# SCH_LED_bar_2021-10-13.net
KiCad netlist of a schematic drawn in EasyEDA
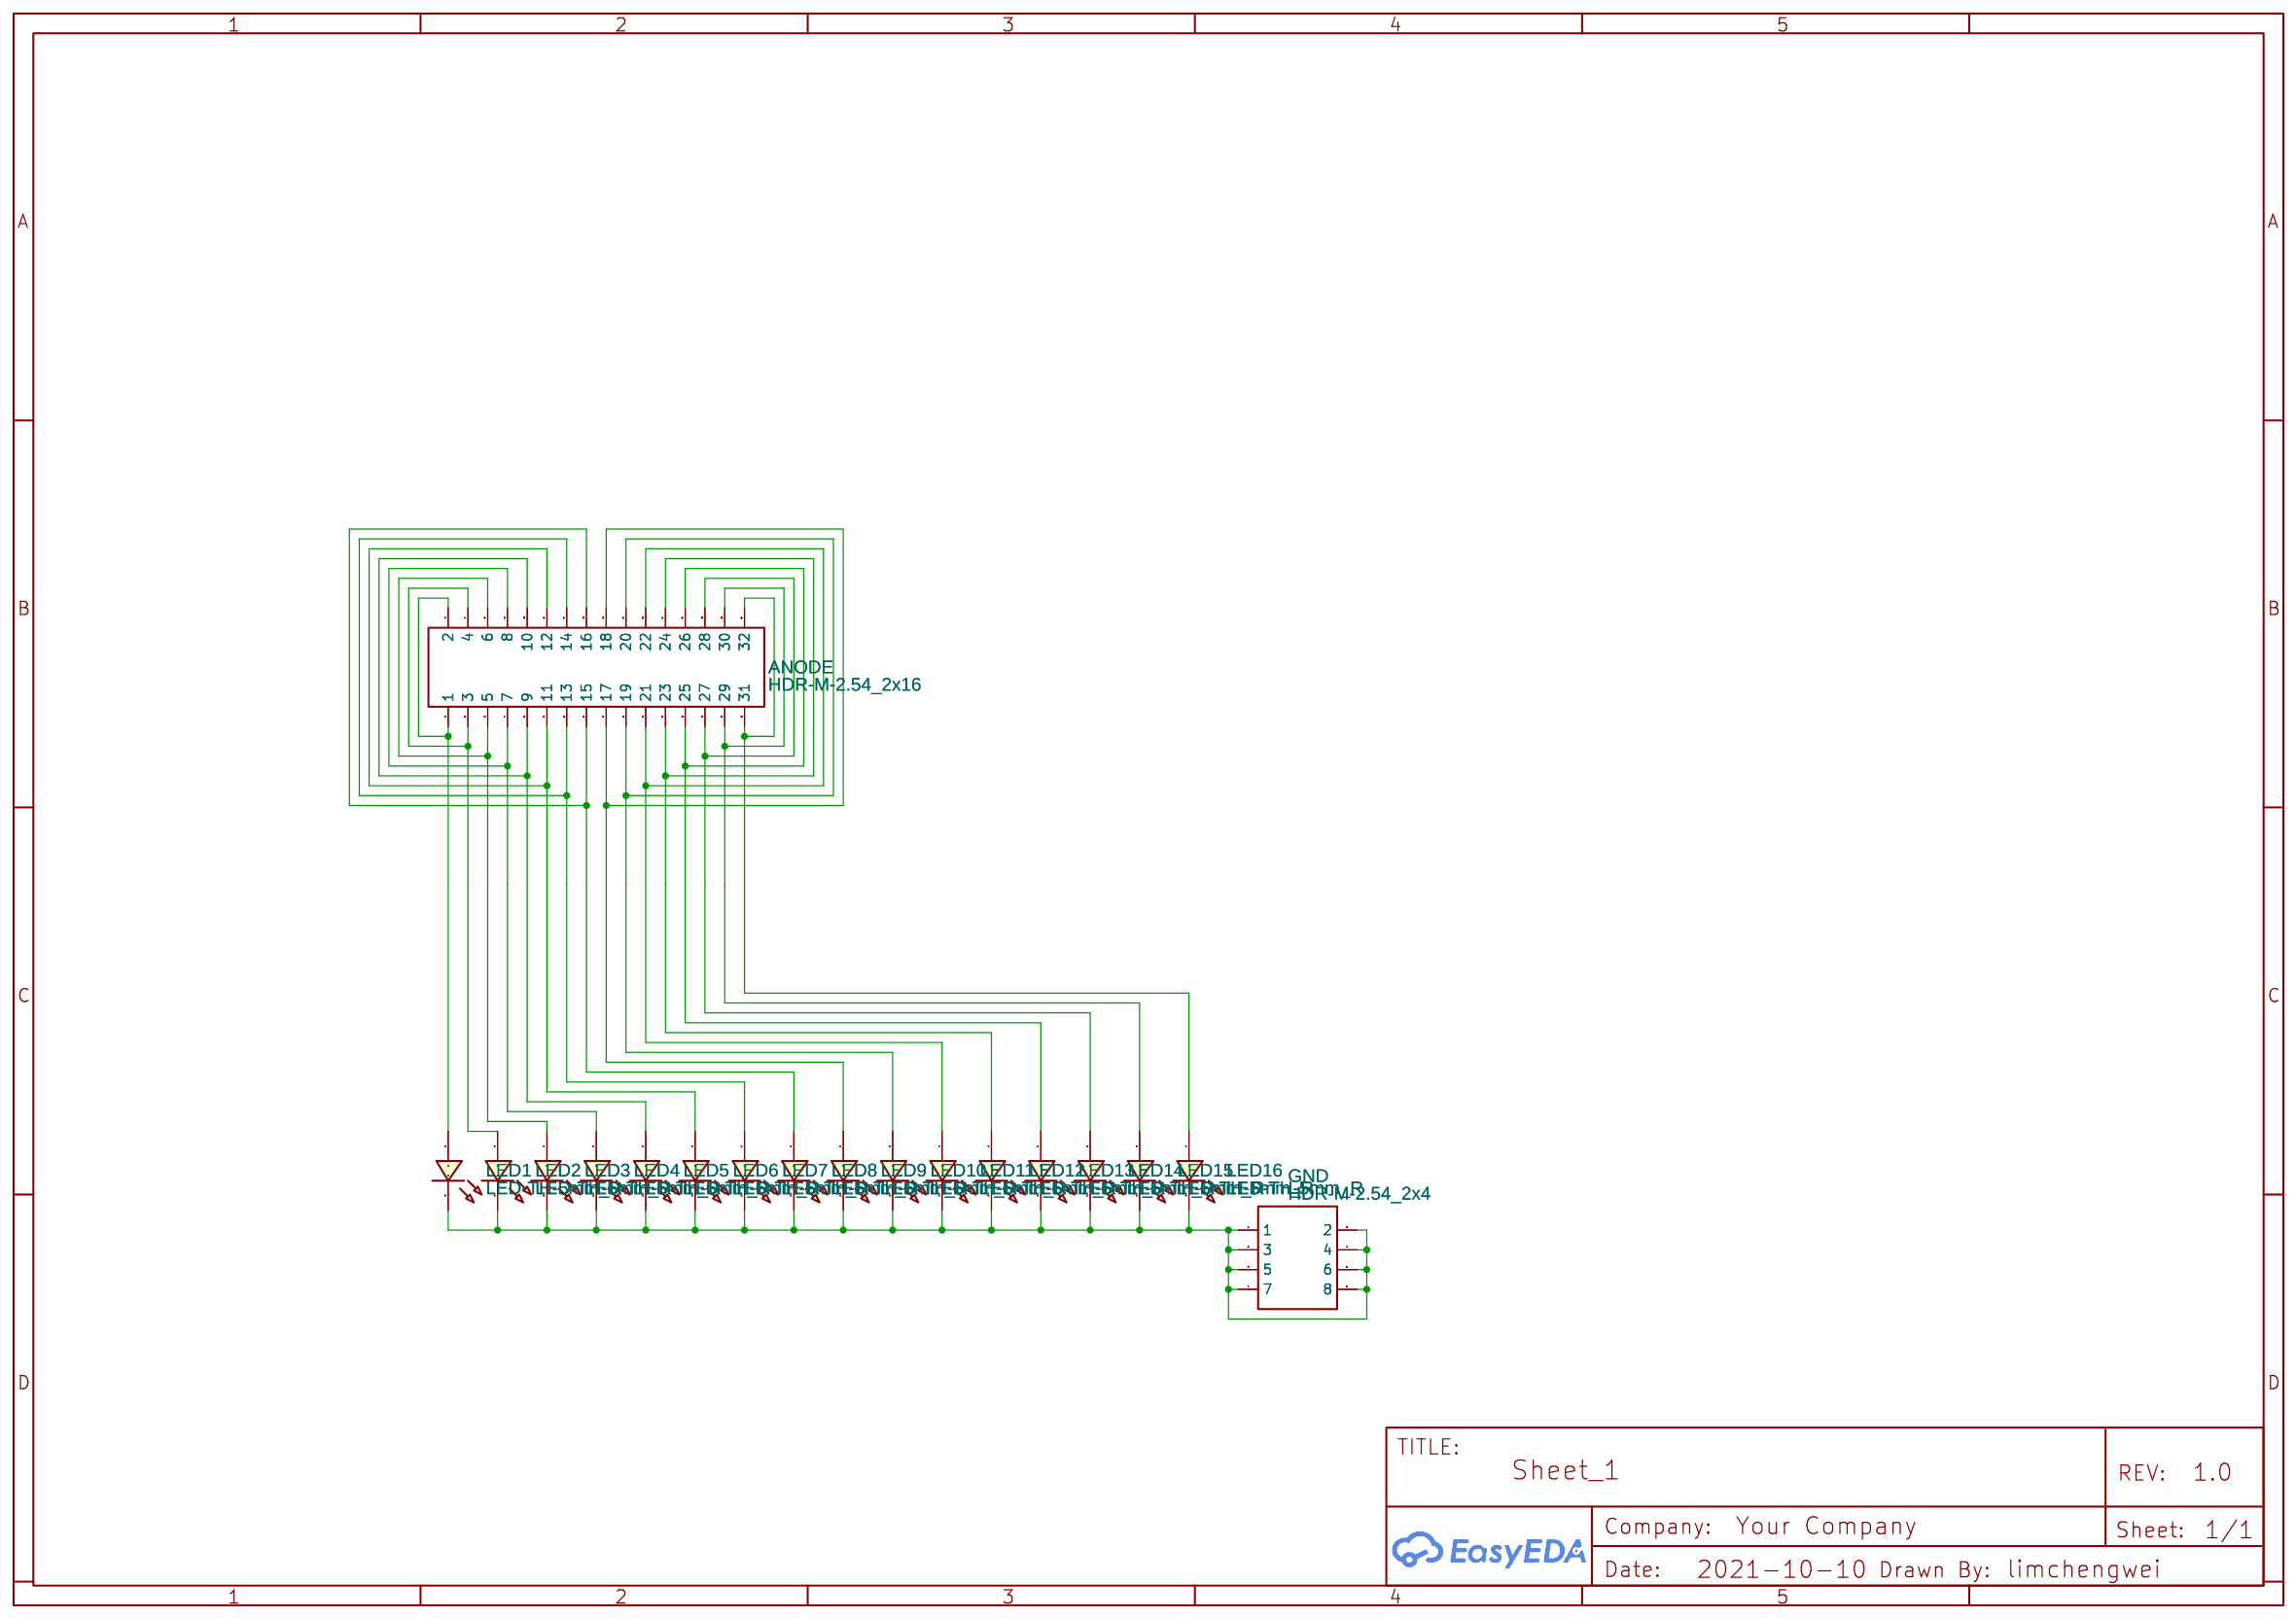
[diagram p0: schematic sheet]

(export (version "E")
  (design (tool "Eeschema 10.0.6"))
  (components
    (comp (ref "ANODE")
      (value "HDR-M-2.54_2x16")
      (fields (field (name "BOM_Supplier Part") "C124382"))
      (libsource (lib "") (part "HDR-M-2.54_2x16"))
    )
    (comp (ref "GND")
      (value "HDR-M-2.54_2x4")
      (fields (field (name "BOM_Supplier Part") "C58363"))
      (libsource (lib "") (part "HDR-M-2.54_2x4"))
    )
    (comp (ref "LED1")
      (value "LED-TH-5mm_R")
      (fields
        (field (name "BOM_Manufacturer Part") "333-2SURD/S530-A3")
        (field (name "BOM_Supplier Part") "C87271")
      )
      (libsource (lib "") (part "LED-TH-5mm_R"))
    )
    (comp (ref "LED2")
      (value "LED-TH-5mm_R")
      (fields
        (field (name "BOM_Manufacturer Part") "333-2SURD/S530-A3")
        (field (name "BOM_Supplier Part") "C87271")
      )
      (libsource (lib "") (part "LED-TH-5mm_R"))
    )
    (comp (ref "LED3")
      (value "LED-TH-5mm_R")
      (fields
        (field (name "BOM_Manufacturer Part") "333-2SURD/S530-A3")
        (field (name "BOM_Supplier Part") "C87271")
      )
      (libsource (lib "") (part "LED-TH-5mm_R"))
    )
    (comp (ref "LED4")
      (value "LED-TH-5mm_R")
      (fields
        (field (name "BOM_Manufacturer Part") "333-2SURD/S530-A3")
        (field (name "BOM_Supplier Part") "C87271")
      )
      (libsource (lib "") (part "LED-TH-5mm_R"))
    )
    (comp (ref "LED5")
      (value "LED-TH-5mm_R")
      (fields
        (field (name "BOM_Manufacturer Part") "333-2SURD/S530-A3")
        (field (name "BOM_Supplier Part") "C87271")
      )
      (libsource (lib "") (part "LED-TH-5mm_R"))
    )
    (comp (ref "LED6")
      (value "LED-TH-5mm_R")
      (fields
        (field (name "BOM_Manufacturer Part") "333-2SURD/S530-A3")
        (field (name "BOM_Supplier Part") "C87271")
      )
      (libsource (lib "") (part "LED-TH-5mm_R"))
    )
    (comp (ref "LED7")
      (value "LED-TH-5mm_R")
      (fields
        (field (name "BOM_Manufacturer Part") "333-2SURD/S530-A3")
        (field (name "BOM_Supplier Part") "C87271")
      )
      (libsource (lib "") (part "LED-TH-5mm_R"))
    )
    (comp (ref "LED8")
      (value "LED-TH-5mm_R")
      (fields
        (field (name "BOM_Manufacturer Part") "333-2SURD/S530-A3")
        (field (name "BOM_Supplier Part") "C87271")
      )
      (libsource (lib "") (part "LED-TH-5mm_R"))
    )
    (comp (ref "LED9")
      (value "LED-TH-5mm_R")
      (fields
        (field (name "BOM_Manufacturer Part") "333-2SURD/S530-A3")
        (field (name "BOM_Supplier Part") "C87271")
      )
      (libsource (lib "") (part "LED-TH-5mm_R"))
    )
    (comp (ref "LED10")
      (value "LED-TH-5mm_R")
      (fields
        (field (name "BOM_Manufacturer Part") "333-2SURD/S530-A3")
        (field (name "BOM_Supplier Part") "C87271")
      )
      (libsource (lib "") (part "LED-TH-5mm_R"))
    )
    (comp (ref "LED11")
      (value "LED-TH-5mm_R")
      (fields
        (field (name "BOM_Manufacturer Part") "333-2SURD/S530-A3")
        (field (name "BOM_Supplier Part") "C87271")
      )
      (libsource (lib "") (part "LED-TH-5mm_R"))
    )
    (comp (ref "LED12")
      (value "LED-TH-5mm_R")
      (fields
        (field (name "BOM_Manufacturer Part") "333-2SURD/S530-A3")
        (field (name "BOM_Supplier Part") "C87271")
      )
      (libsource (lib "") (part "LED-TH-5mm_R"))
    )
    (comp (ref "LED13")
      (value "LED-TH-5mm_R")
      (fields
        (field (name "BOM_Manufacturer Part") "333-2SURD/S530-A3")
        (field (name "BOM_Supplier Part") "C87271")
      )
      (libsource (lib "") (part "LED-TH-5mm_R"))
    )
    (comp (ref "LED14")
      (value "LED-TH-5mm_R")
      (fields
        (field (name "BOM_Manufacturer Part") "333-2SURD/S530-A3")
        (field (name "BOM_Supplier Part") "C87271")
      )
      (libsource (lib "") (part "LED-TH-5mm_R"))
    )
    (comp (ref "LED15")
      (value "LED-TH-5mm_R")
      (fields
        (field (name "BOM_Manufacturer Part") "333-2SURD/S530-A3")
        (field (name "BOM_Supplier Part") "C87271")
      )
      (libsource (lib "") (part "LED-TH-5mm_R"))
    )
    (comp (ref "LED16")
      (value "LED-TH-5mm_R")
      (fields
        (field (name "BOM_Manufacturer Part") "333-2SURD/S530-A3")
        (field (name "BOM_Supplier Part") "C87271")
      )
      (libsource (lib "") (part "LED-TH-5mm_R"))
    )
  )
  (nets
    (net (code "1") (name "Net-(ANODE-Pad1)") (class "Default")
      (node (ref "ANODE") (pin "1") (pinfunction "1_1") (pintype "input"))
      (node (ref "ANODE") (pin "2") (pinfunction "2_2") (pintype "input"))
      (node (ref "LED1") (pin "1") (pinfunction "1_1") (pintype "unspecified"))
    )
    (net (code "2") (name "Net-(ANODE-Pad3)") (class "Default")
      (node (ref "ANODE") (pin "3") (pinfunction "3_3") (pintype "input"))
      (node (ref "ANODE") (pin "4") (pinfunction "4_4") (pintype "input"))
      (node (ref "LED2") (pin "1") (pinfunction "1_1") (pintype "unspecified"))
    )
    (net (code "3") (name "Net-(ANODE-Pad5)") (class "Default")
      (node (ref "ANODE") (pin "5") (pinfunction "5_5") (pintype "input"))
      (node (ref "ANODE") (pin "6") (pinfunction "6_6") (pintype "input"))
      (node (ref "LED3") (pin "1") (pinfunction "1_1") (pintype "unspecified"))
    )
    (net (code "4") (name "Net-(ANODE-Pad7)") (class "Default")
      (node (ref "ANODE") (pin "7") (pinfunction "7_7") (pintype "input"))
      (node (ref "ANODE") (pin "8") (pinfunction "8_8") (pintype "input"))
      (node (ref "LED4") (pin "1") (pinfunction "1_1") (pintype "unspecified"))
    )
    (net (code "5") (name "Net-(ANODE-Pad10)") (class "Default")
      (node (ref "ANODE") (pin "10") (pinfunction "10_10") (pintype "input"))
      (node (ref "ANODE") (pin "9") (pinfunction "9_9") (pintype "input"))
      (node (ref "LED5") (pin "1") (pinfunction "1_1") (pintype "unspecified"))
    )
    (net (code "6") (name "Net-(ANODE-Pad11)") (class "Default")
      (node (ref "ANODE") (pin "11") (pinfunction "11_11") (pintype "input"))
      (node (ref "ANODE") (pin "12") (pinfunction "12_12") (pintype "input"))
      (node (ref "LED6") (pin "1") (pinfunction "1_1") (pintype "unspecified"))
    )
    (net (code "7") (name "Net-(ANODE-Pad13)") (class "Default")
      (node (ref "ANODE") (pin "13") (pinfunction "13_13") (pintype "input"))
      (node (ref "ANODE") (pin "14") (pinfunction "14_14") (pintype "input"))
      (node (ref "LED7") (pin "1") (pinfunction "1_1") (pintype "unspecified"))
    )
    (net (code "8") (name "Net-(ANODE-Pad15)") (class "Default")
      (node (ref "ANODE") (pin "15") (pinfunction "15_15") (pintype "input"))
      (node (ref "ANODE") (pin "16") (pinfunction "16_16") (pintype "input"))
      (node (ref "LED8") (pin "1") (pinfunction "1_1") (pintype "unspecified"))
    )
    (net (code "9") (name "Net-(ANODE-Pad17)") (class "Default")
      (node (ref "ANODE") (pin "17") (pinfunction "17_17") (pintype "input"))
      (node (ref "ANODE") (pin "18") (pinfunction "18_18") (pintype "input"))
      (node (ref "LED9") (pin "1") (pinfunction "1_1") (pintype "unspecified"))
    )
    (net (code "10") (name "Net-(ANODE-Pad19)") (class "Default")
      (node (ref "ANODE") (pin "19") (pinfunction "19_19") (pintype "input"))
      (node (ref "ANODE") (pin "20") (pinfunction "20_20") (pintype "input"))
      (node (ref "LED10") (pin "1") (pinfunction "1_1") (pintype "unspecified"))
    )
    (net (code "11") (name "Net-(ANODE-Pad21)") (class "Default")
      (node (ref "ANODE") (pin "21") (pinfunction "21_21") (pintype "input"))
      (node (ref "ANODE") (pin "22") (pinfunction "22_22") (pintype "input"))
      (node (ref "LED11") (pin "1") (pinfunction "1_1") (pintype "unspecified"))
    )
    (net (code "12") (name "Net-(ANODE-Pad23)") (class "Default")
      (node (ref "ANODE") (pin "23") (pinfunction "23_23") (pintype "input"))
      (node (ref "ANODE") (pin "24") (pinfunction "24_24") (pintype "input"))
      (node (ref "LED12") (pin "1") (pinfunction "1_1") (pintype "unspecified"))
    )
    (net (code "13") (name "Net-(ANODE-Pad25)") (class "Default")
      (node (ref "ANODE") (pin "25") (pinfunction "25_25") (pintype "input"))
      (node (ref "ANODE") (pin "26") (pinfunction "26_26") (pintype "input"))
      (node (ref "LED13") (pin "1") (pinfunction "1_1") (pintype "unspecified"))
    )
    (net (code "14") (name "Net-(ANODE-Pad27)") (class "Default")
      (node (ref "ANODE") (pin "27") (pinfunction "27_27") (pintype "input"))
      (node (ref "ANODE") (pin "28") (pinfunction "28_28") (pintype "input"))
      (node (ref "LED14") (pin "1") (pinfunction "1_1") (pintype "unspecified"))
    )
    (net (code "15") (name "Net-(ANODE-Pad29)") (class "Default")
      (node (ref "ANODE") (pin "29") (pinfunction "29_29") (pintype "input"))
      (node (ref "ANODE") (pin "30") (pinfunction "30_30") (pintype "input"))
      (node (ref "LED15") (pin "1") (pinfunction "1_1") (pintype "unspecified"))
    )
    (net (code "16") (name "Net-(ANODE-Pad31)") (class "Default")
      (node (ref "ANODE") (pin "31") (pinfunction "31_31") (pintype "input"))
      (node (ref "ANODE") (pin "32") (pinfunction "32_32") (pintype "input"))
      (node (ref "LED16") (pin "1") (pinfunction "1_1") (pintype "unspecified"))
    )
    (net (code "17") (name "Net-(GND-Pad1)") (class "Default")
      (node (ref "GND") (pin "1") (pinfunction "1_1") (pintype "unspecified"))
      (node (ref "GND") (pin "2") (pinfunction "2_2") (pintype "unspecified"))
      (node (ref "GND") (pin "3") (pinfunction "3_3") (pintype "unspecified"))
      (node (ref "GND") (pin "4") (pinfunction "4_4") (pintype "unspecified"))
      (node (ref "GND") (pin "5") (pinfunction "5_5") (pintype "unspecified"))
      (node (ref "GND") (pin "6") (pinfunction "6_6") (pintype "unspecified"))
      (node (ref "GND") (pin "7") (pinfunction "7_7") (pintype "unspecified"))
      (node (ref "GND") (pin "8") (pinfunction "8_8") (pintype "unspecified"))
      (node (ref "LED1") (pin "2") (pinfunction "2_2") (pintype "unspecified"))
      (node (ref "LED10") (pin "2") (pinfunction "2_2") (pintype "unspecified"))
      (node (ref "LED11") (pin "2") (pinfunction "2_2") (pintype "unspecified"))
      (node (ref "LED12") (pin "2") (pinfunction "2_2") (pintype "unspecified"))
      (node (ref "LED13") (pin "2") (pinfunction "2_2") (pintype "unspecified"))
      (node (ref "LED14") (pin "2") (pinfunction "2_2") (pintype "unspecified"))
      (node (ref "LED15") (pin "2") (pinfunction "2_2") (pintype "unspecified"))
      (node (ref "LED16") (pin "2") (pinfunction "2_2") (pintype "unspecified"))
      (node (ref "LED2") (pin "2") (pinfunction "2_2") (pintype "unspecified"))
      (node (ref "LED3") (pin "2") (pinfunction "2_2") (pintype "unspecified"))
      (node (ref "LED4") (pin "2") (pinfunction "2_2") (pintype "unspecified"))
      (node (ref "LED5") (pin "2") (pinfunction "2_2") (pintype "unspecified"))
      (node (ref "LED6") (pin "2") (pinfunction "2_2") (pintype "unspecified"))
      (node (ref "LED7") (pin "2") (pinfunction "2_2") (pintype "unspecified"))
      (node (ref "LED8") (pin "2") (pinfunction "2_2") (pintype "unspecified"))
      (node (ref "LED9") (pin "2") (pinfunction "2_2") (pintype "unspecified"))
    )
  )
)
